# TopLevel.net
KiCad netlist of a schematic drawn in Altium Designer
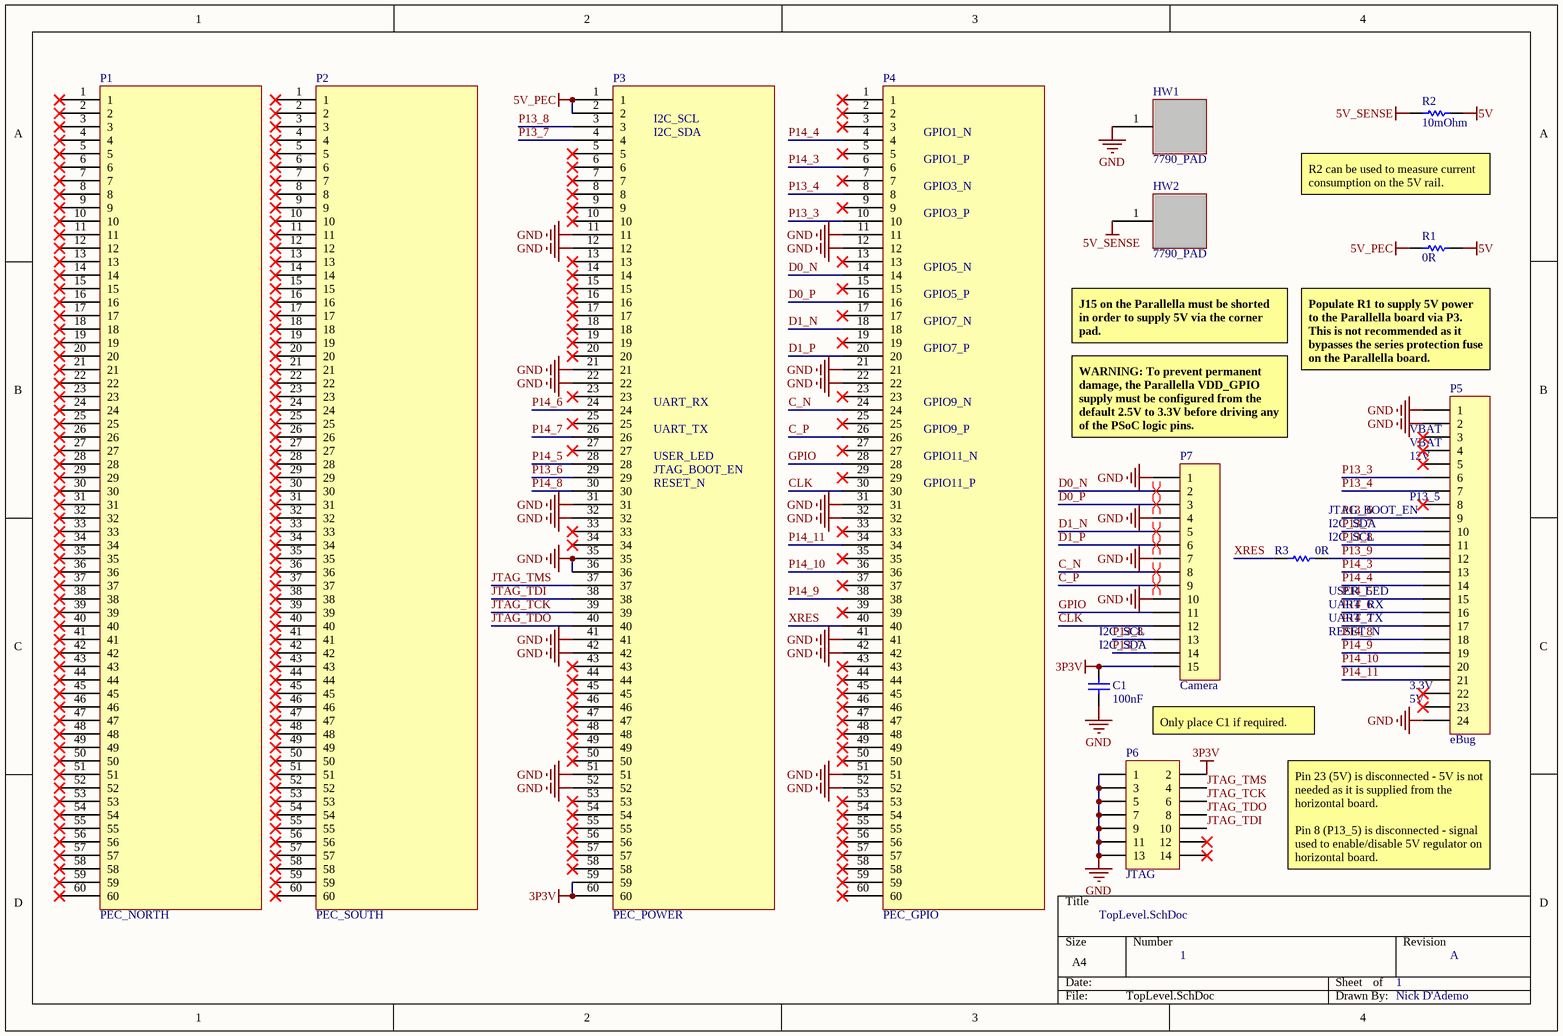
[diagram p0: TopLevel.SchDoc]

(export (version "E")
  (design (tool "Eeschema 10.0.6"))
  (components
    (comp (ref "C1")
      (value "100nF")
      (footprint "CAPC1005N")
      (description "Capacitor, X7R, ±10%, 16V, 0402")
      (fields (field (name "Comment") "Cap") (field (name "PUBLISHER") "Altium Limited"))
      (libsource (lib "Miscellaneous Devices") (part "Cap"))
    )
    (comp (ref "HW1")
      (value "7790_PAD")
      (footprint "7790_PAD")
      (libsource (lib "eBug2014-Parallella-Carrier-V") (part "7790_PAD"))
    )
    (comp (ref "HW2")
      (value "7790_PAD")
      (footprint "7790_PAD")
      (libsource (lib "eBug2014-Parallella-Carrier-V") (part "7790_PAD"))
    )
    (comp (ref "P1")
      (value "PEC_NORTH")
      (footprint "BTH-030-01-F-D-A")
      (description "SAMTEC - BTH-030-01-F-D-A - Conn Micro Terminal HDR 60 POS 0.5mm")
      (libsource (lib "eBug2014-Parallella-Carrier-V") (part "BTH-030-01-F-D-A"))
    )
    (comp (ref "P2")
      (value "PEC_SOUTH")
      (footprint "BTH-030-01-F-D-A")
      (description "SAMTEC - BTH-030-01-F-D-A - Conn Micro Terminal HDR 60 POS 0.5mm")
      (libsource (lib "eBug2014-Parallella-Carrier-V") (part "BTH-030-01-F-D-A"))
    )
    (comp (ref "P3")
      (value "PEC_POWER")
      (footprint "BTH-030-01-F-D-A")
      (description "SAMTEC - BTH-030-01-F-D-A - Conn Micro Terminal HDR 60 POS 0.5mm")
      (libsource (lib "eBug2014-Parallella-Carrier-V") (part "BTH-030-01-F-D-A"))
    )
    (comp (ref "P4")
      (value "PEC_GPIO")
      (footprint "BTH-030-01-F-D-A")
      (description "SAMTEC - BTH-030-01-F-D-A - Conn Micro Terminal HDR 60 POS 0.5mm")
      (libsource (lib "eBug2014-Parallella-Carrier-V") (part "BTH-030-01-F-D-A"))
    )
    (comp (ref "P5")
      (value "eBug")
      (footprint "2-1734592-4_MIRRORED")
      (description "TE CONNECTIVITY - 2-1734592-4 - CONN FPC BOTTOM 24POS 0.50MM R/A")
      (fields (field (name "PUBLISHER") "Altium Limited"))
      (libsource (lib "Miscellaneous Connectors") (part "Header 24"))
    )
    (comp (ref "P6")
      (value "JTAG")
      (footprint "2x7H_2mm")
      (description "Header, 7-Pin, Dual row")
      (fields (field (name "PUBLISHER") "Altium Limited"))
      (libsource (lib "Miscellaneous Connectors") (part "Header 7X2"))
    )
    (comp (ref "P7")
      (value "Camera")
      (footprint "1-1734248-5")
      (fields (field (name "PUBLISHER") "Altium Limited"))
      (libsource (lib "Miscellaneous Connectors") (part "Header 15"))
    )
    (comp (ref "R1")
      (value "0R")
      (footprint "RESC1608M")
      (description "Resistor, ±1%, 0.1W, 0603")
      (fields (field (name "Comment") "Jumper Resistor") (field (name "PUBLISHER") "Altium Limited"))
      (libsource (lib "Miscellaneous Devices") (part "Res1"))
    )
    (comp (ref "R2")
      (value "10mOhm")
      (footprint "RESC6432M")
      (fields (field (name "Comment") "Current Sense Resistor") (field (name "PUBLISHER") "Altium Limited"))
      (libsource (lib "Miscellaneous Devices") (part "Res1"))
    )
    (comp (ref "R3")
      (value "0R")
      (footprint "RESC1608M")
      (description "Resistor, ±1%, 0.1W, 0603")
      (fields (field (name "Comment") "Jumper Resistor") (field (name "PUBLISHER") "Altium Limited"))
      (libsource (lib "Miscellaneous Devices") (part "Res1"))
    )
  )
  (nets
    (net (code "1") (name "/CLK") (class "Default")
      (node (ref "P4") (pin "30") (pinfunction "30_30") (pintype "passive"))
      (node (ref "P7") (pin "12") (pinfunction "12_12") (pintype "passive"))
    )
    (net (code "2") (name "/C_N") (class "Default")
      (node (ref "P4") (pin "24") (pinfunction "24_24") (pintype "passive"))
      (node (ref "P7") (pin "8") (pinfunction "8_8") (pintype "passive"))
    )
    (net (code "3") (name "/C_P") (class "Default")
      (node (ref "P4") (pin "26") (pinfunction "26_26") (pintype "passive"))
      (node (ref "P7") (pin "9") (pinfunction "9_9") (pintype "passive"))
    )
    (net (code "4") (name "/D0_N") (class "Default")
      (node (ref "P4") (pin "14") (pinfunction "14_14") (pintype "passive"))
      (node (ref "P7") (pin "2") (pinfunction "2_2") (pintype "passive"))
    )
    (net (code "5") (name "/D0_P") (class "Default")
      (node (ref "P4") (pin "16") (pinfunction "16_16") (pintype "passive"))
      (node (ref "P7") (pin "3") (pinfunction "3_3") (pintype "passive"))
    )
    (net (code "6") (name "/D1_N") (class "Default")
      (node (ref "P4") (pin "18") (pinfunction "18_18") (pintype "passive"))
      (node (ref "P7") (pin "5") (pinfunction "5_5") (pintype "passive"))
    )
    (net (code "7") (name "/D1_P") (class "Default")
      (node (ref "P4") (pin "20") (pinfunction "20_20") (pintype "passive"))
      (node (ref "P7") (pin "6") (pinfunction "6_6") (pintype "passive"))
    )
    (net (code "8") (name "/GPIO") (class "Default")
      (node (ref "P4") (pin "28") (pinfunction "28_28") (pintype "passive"))
      (node (ref "P7") (pin "11") (pinfunction "11_11") (pintype "passive"))
    )
    (net (code "9") (name "/JTAG_TCK") (class "Default")
      (node (ref "P3") (pin "39") (pinfunction "39_39") (pintype "passive"))
      (node (ref "P6") (pin "6") (pinfunction "6_6") (pintype "passive"))
    )
    (net (code "10") (name "/JTAG_TDI") (class "Default")
      (node (ref "P3") (pin "38") (pinfunction "38_38") (pintype "passive"))
      (node (ref "P6") (pin "10") (pinfunction "10_10") (pintype "passive"))
    )
    (net (code "11") (name "/JTAG_TDO") (class "Default")
      (node (ref "P3") (pin "40") (pinfunction "40_40") (pintype "passive"))
      (node (ref "P6") (pin "8") (pinfunction "8_8") (pintype "passive"))
    )
    (net (code "12") (name "/JTAG_TMS") (class "Default")
      (node (ref "P3") (pin "37") (pinfunction "37_37") (pintype "passive"))
      (node (ref "P6") (pin "4") (pinfunction "4_4") (pintype "passive"))
    )
    (net (code "13") (name "/P13_3") (class "Default")
      (node (ref "P4") (pin "10") (pinfunction "10_10") (pintype "passive"))
      (node (ref "P5") (pin "6") (pinfunction "6_6") (pintype "passive"))
    )
    (net (code "14") (name "/P13_4") (class "Default")
      (node (ref "P4") (pin "8") (pinfunction "8_8") (pintype "passive"))
      (node (ref "P5") (pin "7") (pinfunction "7_7") (pintype "passive"))
    )
    (net (code "15") (name "/P13_6") (class "Default")
      (node (ref "P3") (pin "29") (pinfunction "29_29") (pintype "passive"))
      (node (ref "P5") (pin "9") (pinfunction "9_9") (pintype "passive"))
    )
    (net (code "16") (name "/P13_7") (class "Default")
      (node (ref "P3") (pin "4") (pinfunction "4_4") (pintype "passive"))
      (node (ref "P5") (pin "10") (pinfunction "10_10") (pintype "passive"))
      (node (ref "P7") (pin "14") (pinfunction "14_14") (pintype "passive"))
    )
    (net (code "17") (name "/P13_8") (class "Default")
      (node (ref "P3") (pin "3") (pinfunction "3_3") (pintype "passive"))
      (node (ref "P5") (pin "11") (pinfunction "11_11") (pintype "passive"))
      (node (ref "P7") (pin "13") (pinfunction "13_13") (pintype "passive"))
    )
    (net (code "18") (name "/P13_9") (class "Default")
      (node (ref "P5") (pin "12") (pinfunction "12_12") (pintype "passive"))
      (node (ref "R3") (pin "1") (pinfunction "1_1") (pintype "passive"))
    )
    (net (code "19") (name "/P14_3") (class "Default")
      (node (ref "P4") (pin "6") (pinfunction "6_6") (pintype "passive"))
      (node (ref "P5") (pin "13") (pinfunction "13_13") (pintype "passive"))
    )
    (net (code "20") (name "/P14_4") (class "Default")
      (node (ref "P4") (pin "4") (pinfunction "4_4") (pintype "passive"))
      (node (ref "P5") (pin "14") (pinfunction "14_14") (pintype "passive"))
    )
    (net (code "21") (name "/P14_5") (class "Default")
      (node (ref "P3") (pin "28") (pinfunction "28_28") (pintype "passive"))
      (node (ref "P5") (pin "15") (pinfunction "15_15") (pintype "passive"))
    )
    (net (code "22") (name "/P14_6") (class "Default")
      (node (ref "P3") (pin "24") (pinfunction "24_24") (pintype "passive"))
      (node (ref "P5") (pin "16") (pinfunction "16_16") (pintype "passive"))
    )
    (net (code "23") (name "/P14_7") (class "Default")
      (node (ref "P3") (pin "26") (pinfunction "26_26") (pintype "passive"))
      (node (ref "P5") (pin "17") (pinfunction "17_17") (pintype "passive"))
    )
    (net (code "24") (name "/P14_8") (class "Default")
      (node (ref "P3") (pin "30") (pinfunction "30_30") (pintype "passive"))
      (node (ref "P5") (pin "18") (pinfunction "18_18") (pintype "passive"))
    )
    (net (code "25") (name "/P14_9") (class "Default")
      (node (ref "P4") (pin "38") (pinfunction "38_38") (pintype "passive"))
      (node (ref "P5") (pin "19") (pinfunction "19_19") (pintype "passive"))
    )
    (net (code "26") (name "/P14_10") (class "Default")
      (node (ref "P4") (pin "36") (pinfunction "36_36") (pintype "passive"))
      (node (ref "P5") (pin "20") (pinfunction "20_20") (pintype "passive"))
    )
    (net (code "27") (name "/P14_11") (class "Default")
      (node (ref "P4") (pin "34") (pinfunction "34_34") (pintype "passive"))
      (node (ref "P5") (pin "21") (pinfunction "21_21") (pintype "passive"))
    )
    (net (code "28") (name "/XRES") (class "Default")
      (node (ref "P4") (pin "40") (pinfunction "40_40") (pintype "passive"))
      (node (ref "R3") (pin "2") (pinfunction "2_2") (pintype "passive"))
    )
    (net (code "29") (name "3P3V") (class "Default")
      (node (ref "C1") (pin "2") (pinfunction "2_2") (pintype "passive"))
      (node (ref "P3") (pin "59") (pinfunction "59_59") (pintype "passive"))
      (node (ref "P3") (pin "60") (pinfunction "60_60") (pintype "passive"))
      (node (ref "P6") (pin "2") (pinfunction "2_2") (pintype "passive"))
      (node (ref "P7") (pin "15") (pinfunction "15_15") (pintype "passive"))
    )
    (net (code "30") (name "5V") (class "Default")
      (node (ref "R1") (pin "1") (pinfunction "1_1") (pintype "passive"))
      (node (ref "R2") (pin "1") (pinfunction "1_1") (pintype "passive"))
    )
    (net (code "31") (name "5V_PEC") (class "Default")
      (node (ref "P3") (pin "1") (pinfunction "1_1") (pintype "passive"))
      (node (ref "P3") (pin "2") (pinfunction "2_2") (pintype "passive"))
      (node (ref "R1") (pin "2") (pinfunction "2_2") (pintype "passive"))
    )
    (net (code "32") (name "5V_SENSE") (class "Default")
      (node (ref "HW2") (pin "1") (pintype "passive"))
      (node (ref "R2") (pin "2") (pinfunction "2_2") (pintype "passive"))
    )
    (net (code "33") (name "GND") (class "Default")
      (node (ref "C1") (pin "1") (pinfunction "1_1") (pintype "passive"))
      (node (ref "HW1") (pin "1") (pintype "passive"))
      (node (ref "P3") (pin "11") (pinfunction "11_11") (pintype "passive"))
      (node (ref "P3") (pin "12") (pinfunction "12_12") (pintype "passive"))
      (node (ref "P3") (pin "21") (pinfunction "21_21") (pintype "passive"))
      (node (ref "P3") (pin "22") (pinfunction "22_22") (pintype "passive"))
      (node (ref "P3") (pin "31") (pinfunction "31_31") (pintype "passive"))
      (node (ref "P3") (pin "32") (pinfunction "32_32") (pintype "passive"))
      (node (ref "P3") (pin "35") (pinfunction "35_35") (pintype "passive"))
      (node (ref "P3") (pin "36") (pinfunction "36_36") (pintype "passive"))
      (node (ref "P3") (pin "41") (pinfunction "41_41") (pintype "passive"))
      (node (ref "P3") (pin "42") (pinfunction "42_42") (pintype "passive"))
      (node (ref "P3") (pin "51") (pinfunction "51_51") (pintype "passive"))
      (node (ref "P3") (pin "52") (pinfunction "52_52") (pintype "passive"))
      (node (ref "P4") (pin "11") (pinfunction "11_11") (pintype "passive"))
      (node (ref "P4") (pin "12") (pinfunction "12_12") (pintype "passive"))
      (node (ref "P4") (pin "21") (pinfunction "21_21") (pintype "passive"))
      (node (ref "P4") (pin "22") (pinfunction "22_22") (pintype "passive"))
      (node (ref "P4") (pin "31") (pinfunction "31_31") (pintype "passive"))
      (node (ref "P4") (pin "32") (pinfunction "32_32") (pintype "passive"))
      (node (ref "P4") (pin "41") (pinfunction "41_41") (pintype "passive"))
      (node (ref "P4") (pin "42") (pinfunction "42_42") (pintype "passive"))
      (node (ref "P4") (pin "51") (pinfunction "51_51") (pintype "passive"))
      (node (ref "P4") (pin "52") (pinfunction "52_52") (pintype "passive"))
      (node (ref "P5") (pin "1") (pinfunction "1_1") (pintype "passive"))
      (node (ref "P5") (pin "2") (pinfunction "2_2") (pintype "passive"))
      (node (ref "P5") (pin "24") (pinfunction "24_24") (pintype "passive"))
      (node (ref "P6") (pin "1") (pinfunction "1_1") (pintype "passive"))
      (node (ref "P6") (pin "11") (pinfunction "11_11") (pintype "passive"))
      (node (ref "P6") (pin "13") (pinfunction "13_13") (pintype "passive"))
      (node (ref "P6") (pin "3") (pinfunction "3_3") (pintype "passive"))
      (node (ref "P6") (pin "5") (pinfunction "5_5") (pintype "passive"))
      (node (ref "P6") (pin "7") (pinfunction "7_7") (pintype "passive"))
      (node (ref "P6") (pin "9") (pinfunction "9_9") (pintype "passive"))
      (node (ref "P7") (pin "1") (pinfunction "1_1") (pintype "passive"))
      (node (ref "P7") (pin "10") (pinfunction "10_10") (pintype "passive"))
      (node (ref "P7") (pin "4") (pinfunction "4_4") (pintype "passive"))
      (node (ref "P7") (pin "7") (pinfunction "7_7") (pintype "passive"))
    )
    (net (code "34") (name "unconnected-(P1-Pad1)") (class "Default")
      (node (ref "P1") (pin "1") (pinfunction "1_1") (pintype "passive+no_connect"))
    )
    (net (code "35") (name "unconnected-(P1-Pad2)") (class "Default")
      (node (ref "P1") (pin "2") (pinfunction "2_2") (pintype "passive+no_connect"))
    )
    (net (code "36") (name "unconnected-(P1-Pad3)") (class "Default")
      (node (ref "P1") (pin "3") (pinfunction "3_3") (pintype "passive+no_connect"))
    )
    (net (code "37") (name "unconnected-(P1-Pad4)") (class "Default")
      (node (ref "P1") (pin "4") (pinfunction "4_4") (pintype "passive+no_connect"))
    )
    (net (code "38") (name "unconnected-(P1-Pad5)") (class "Default")
      (node (ref "P1") (pin "5") (pinfunction "5_5") (pintype "passive+no_connect"))
    )
    (net (code "39") (name "unconnected-(P1-Pad6)") (class "Default")
      (node (ref "P1") (pin "6") (pinfunction "6_6") (pintype "passive+no_connect"))
    )
    (net (code "40") (name "unconnected-(P1-Pad7)") (class "Default")
      (node (ref "P1") (pin "7") (pinfunction "7_7") (pintype "passive+no_connect"))
    )
    (net (code "41") (name "unconnected-(P1-Pad8)") (class "Default")
      (node (ref "P1") (pin "8") (pinfunction "8_8") (pintype "passive+no_connect"))
    )
    (net (code "42") (name "unconnected-(P1-Pad9)") (class "Default")
      (node (ref "P1") (pin "9") (pinfunction "9_9") (pintype "passive+no_connect"))
    )
    (net (code "43") (name "unconnected-(P1-Pad10)") (class "Default")
      (node (ref "P1") (pin "10") (pinfunction "10_10") (pintype "passive+no_connect"))
    )
    (net (code "44") (name "unconnected-(P1-Pad11)") (class "Default")
      (node (ref "P1") (pin "11") (pinfunction "11_11") (pintype "passive+no_connect"))
    )
    (net (code "45") (name "unconnected-(P1-Pad12)") (class "Default")
      (node (ref "P1") (pin "12") (pinfunction "12_12") (pintype "passive+no_connect"))
    )
    (net (code "46") (name "unconnected-(P1-Pad13)") (class "Default")
      (node (ref "P1") (pin "13") (pinfunction "13_13") (pintype "passive+no_connect"))
    )
    (net (code "47") (name "unconnected-(P1-Pad14)") (class "Default")
      (node (ref "P1") (pin "14") (pinfunction "14_14") (pintype "passive+no_connect"))
    )
    (net (code "48") (name "unconnected-(P1-Pad15)") (class "Default")
      (node (ref "P1") (pin "15") (pinfunction "15_15") (pintype "passive+no_connect"))
    )
    (net (code "49") (name "unconnected-(P1-Pad16)") (class "Default")
      (node (ref "P1") (pin "16") (pinfunction "16_16") (pintype "passive+no_connect"))
    )
    (net (code "50") (name "unconnected-(P1-Pad17)") (class "Default")
      (node (ref "P1") (pin "17") (pinfunction "17_17") (pintype "passive+no_connect"))
    )
    (net (code "51") (name "unconnected-(P1-Pad18)") (class "Default")
      (node (ref "P1") (pin "18") (pinfunction "18_18") (pintype "passive+no_connect"))
    )
    (net (code "52") (name "unconnected-(P1-Pad19)") (class "Default")
      (node (ref "P1") (pin "19") (pinfunction "19_19") (pintype "passive+no_connect"))
    )
    (net (code "53") (name "unconnected-(P1-Pad20)") (class "Default")
      (node (ref "P1") (pin "20") (pinfunction "20_20") (pintype "passive+no_connect"))
    )
    (net (code "54") (name "unconnected-(P1-Pad21)") (class "Default")
      (node (ref "P1") (pin "21") (pinfunction "21_21") (pintype "passive+no_connect"))
    )
    (net (code "55") (name "unconnected-(P1-Pad22)") (class "Default")
      (node (ref "P1") (pin "22") (pinfunction "22_22") (pintype "passive+no_connect"))
    )
    (net (code "56") (name "unconnected-(P1-Pad23)") (class "Default")
      (node (ref "P1") (pin "23") (pinfunction "23_23") (pintype "passive+no_connect"))
    )
    (net (code "57") (name "unconnected-(P1-Pad24)") (class "Default")
      (node (ref "P1") (pin "24") (pinfunction "24_24") (pintype "passive+no_connect"))
    )
    (net (code "58") (name "unconnected-(P1-Pad25)") (class "Default")
      (node (ref "P1") (pin "25") (pinfunction "25_25") (pintype "passive+no_connect"))
    )
    (net (code "59") (name "unconnected-(P1-Pad26)") (class "Default")
      (node (ref "P1") (pin "26") (pinfunction "26_26") (pintype "passive+no_connect"))
    )
    (net (code "60") (name "unconnected-(P1-Pad27)") (class "Default")
      (node (ref "P1") (pin "27") (pinfunction "27_27") (pintype "passive+no_connect"))
    )
    (net (code "61") (name "unconnected-(P1-Pad28)") (class "Default")
      (node (ref "P1") (pin "28") (pinfunction "28_28") (pintype "passive+no_connect"))
    )
    (net (code "62") (name "unconnected-(P1-Pad29)") (class "Default")
      (node (ref "P1") (pin "29") (pinfunction "29_29") (pintype "passive+no_connect"))
    )
    (net (code "63") (name "unconnected-(P1-Pad30)") (class "Default")
      (node (ref "P1") (pin "30") (pinfunction "30_30") (pintype "passive+no_connect"))
    )
    (net (code "64") (name "unconnected-(P1-Pad31)") (class "Default")
      (node (ref "P1") (pin "31") (pinfunction "31_31") (pintype "passive+no_connect"))
    )
    (net (code "65") (name "unconnected-(P1-Pad32)") (class "Default")
      (node (ref "P1") (pin "32") (pinfunction "32_32") (pintype "passive+no_connect"))
    )
    (net (code "66") (name "unconnected-(P1-Pad33)") (class "Default")
      (node (ref "P1") (pin "33") (pinfunction "33_33") (pintype "passive+no_connect"))
    )
    (net (code "67") (name "unconnected-(P1-Pad34)") (class "Default")
      (node (ref "P1") (pin "34") (pinfunction "34_34") (pintype "passive+no_connect"))
    )
    (net (code "68") (name "unconnected-(P1-Pad35)") (class "Default")
      (node (ref "P1") (pin "35") (pinfunction "35_35") (pintype "passive+no_connect"))
    )
    (net (code "69") (name "unconnected-(P1-Pad36)") (class "Default")
      (node (ref "P1") (pin "36") (pinfunction "36_36") (pintype "passive+no_connect"))
    )
    (net (code "70") (name "unconnected-(P1-Pad37)") (class "Default")
      (node (ref "P1") (pin "37") (pinfunction "37_37") (pintype "passive+no_connect"))
    )
    (net (code "71") (name "unconnected-(P1-Pad38)") (class "Default")
      (node (ref "P1") (pin "38") (pinfunction "38_38") (pintype "passive+no_connect"))
    )
    (net (code "72") (name "unconnected-(P1-Pad39)") (class "Default")
      (node (ref "P1") (pin "39") (pinfunction "39_39") (pintype "passive+no_connect"))
    )
    (net (code "73") (name "unconnected-(P1-Pad40)") (class "Default")
      (node (ref "P1") (pin "40") (pinfunction "40_40") (pintype "passive+no_connect"))
    )
    (net (code "74") (name "unconnected-(P1-Pad41)") (class "Default")
      (node (ref "P1") (pin "41") (pinfunction "41_41") (pintype "passive+no_connect"))
    )
    (net (code "75") (name "unconnected-(P1-Pad42)") (class "Default")
      (node (ref "P1") (pin "42") (pinfunction "42_42") (pintype "passive+no_connect"))
    )
    (net (code "76") (name "unconnected-(P1-Pad43)") (class "Default")
      (node (ref "P1") (pin "43") (pinfunction "43_43") (pintype "passive+no_connect"))
    )
    (net (code "77") (name "unconnected-(P1-Pad44)") (class "Default")
      (node (ref "P1") (pin "44") (pinfunction "44_44") (pintype "passive+no_connect"))
    )
    (net (code "78") (name "unconnected-(P1-Pad45)") (class "Default")
      (node (ref "P1") (pin "45") (pinfunction "45_45") (pintype "passive+no_connect"))
    )
    (net (code "79") (name "unconnected-(P1-Pad46)") (class "Default")
      (node (ref "P1") (pin "46") (pinfunction "46_46") (pintype "passive+no_connect"))
    )
    (net (code "80") (name "unconnected-(P1-Pad47)") (class "Default")
      (node (ref "P1") (pin "47") (pinfunction "47_47") (pintype "passive+no_connect"))
    )
    (net (code "81") (name "unconnected-(P1-Pad48)") (class "Default")
      (node (ref "P1") (pin "48") (pinfunction "48_48") (pintype "passive+no_connect"))
    )
    (net (code "82") (name "unconnected-(P1-Pad49)") (class "Default")
      (node (ref "P1") (pin "49") (pinfunction "49_49") (pintype "passive+no_connect"))
    )
    (net (code "83") (name "unconnected-(P1-Pad50)") (class "Default")
      (node (ref "P1") (pin "50") (pinfunction "50_50") (pintype "passive+no_connect"))
    )
    (net (code "84") (name "unconnected-(P1-Pad51)") (class "Default")
      (node (ref "P1") (pin "51") (pinfunction "51_51") (pintype "passive+no_connect"))
    )
    (net (code "85") (name "unconnected-(P1-Pad52)") (class "Default")
      (node (ref "P1") (pin "52") (pinfunction "52_52") (pintype "passive+no_connect"))
    )
    (net (code "86") (name "unconnected-(P1-Pad53)") (class "Default")
      (node (ref "P1") (pin "53") (pinfunction "53_53") (pintype "passive+no_connect"))
    )
    (net (code "87") (name "unconnected-(P1-Pad54)") (class "Default")
      (node (ref "P1") (pin "54") (pinfunction "54_54") (pintype "passive+no_connect"))
    )
    (net (code "88") (name "unconnected-(P1-Pad55)") (class "Default")
      (node (ref "P1") (pin "55") (pinfunction "55_55") (pintype "passive+no_connect"))
    )
    (net (code "89") (name "unconnected-(P1-Pad56)") (class "Default")
      (node (ref "P1") (pin "56") (pinfunction "56_56") (pintype "passive+no_connect"))
    )
    (net (code "90") (name "unconnected-(P1-Pad57)") (class "Default")
      (node (ref "P1") (pin "57") (pinfunction "57_57") (pintype "passive+no_connect"))
    )
    (net (code "91") (name "unconnected-(P1-Pad58)") (class "Default")
      (node (ref "P1") (pin "58") (pinfunction "58_58") (pintype "passive+no_connect"))
    )
    (net (code "92") (name "unconnected-(P1-Pad59)") (class "Default")
      (node (ref "P1") (pin "59") (pinfunction "59_59") (pintype "passive+no_connect"))
    )
    (net (code "93") (name "unconnected-(P1-Pad60)") (class "Default")
      (node (ref "P1") (pin "60") (pinfunction "60_60") (pintype "passive+no_connect"))
    )
    (net (code "94") (name "unconnected-(P2-Pad1)") (class "Default")
      (node (ref "P2") (pin "1") (pinfunction "1_1") (pintype "passive+no_connect"))
    )
    (net (code "95") (name "unconnected-(P2-Pad2)") (class "Default")
      (node (ref "P2") (pin "2") (pinfunction "2_2") (pintype "passive+no_connect"))
    )
    (net (code "96") (name "unconnected-(P2-Pad3)") (class "Default")
      (node (ref "P2") (pin "3") (pinfunction "3_3") (pintype "passive+no_connect"))
    )
    (net (code "97") (name "unconnected-(P2-Pad4)") (class "Default")
      (node (ref "P2") (pin "4") (pinfunction "4_4") (pintype "passive+no_connect"))
    )
    (net (code "98") (name "unconnected-(P2-Pad5)") (class "Default")
      (node (ref "P2") (pin "5") (pinfunction "5_5") (pintype "passive+no_connect"))
    )
    (net (code "99") (name "unconnected-(P2-Pad6)") (class "Default")
      (node (ref "P2") (pin "6") (pinfunction "6_6") (pintype "passive+no_connect"))
    )
    (net (code "100") (name "unconnected-(P2-Pad7)") (class "Default")
      (node (ref "P2") (pin "7") (pinfunction "7_7") (pintype "passive+no_connect"))
    )
    (net (code "101") (name "unconnected-(P2-Pad8)") (class "Default")
      (node (ref "P2") (pin "8") (pinfunction "8_8") (pintype "passive+no_connect"))
    )
    (net (code "102") (name "unconnected-(P2-Pad9)") (class "Default")
      (node (ref "P2") (pin "9") (pinfunction "9_9") (pintype "passive+no_connect"))
    )
    (net (code "103") (name "unconnected-(P2-Pad10)") (class "Default")
      (node (ref "P2") (pin "10") (pinfunction "10_10") (pintype "passive+no_connect"))
    )
    (net (code "104") (name "unconnected-(P2-Pad11)") (class "Default")
      (node (ref "P2") (pin "11") (pinfunction "11_11") (pintype "passive+no_connect"))
    )
    (net (code "105") (name "unconnected-(P2-Pad12)") (class "Default")
      (node (ref "P2") (pin "12") (pinfunction "12_12") (pintype "passive+no_connect"))
    )
    (net (code "106") (name "unconnected-(P2-Pad13)") (class "Default")
      (node (ref "P2") (pin "13") (pinfunction "13_13") (pintype "passive+no_connect"))
    )
    (net (code "107") (name "unconnected-(P2-Pad14)") (class "Default")
      (node (ref "P2") (pin "14") (pinfunction "14_14") (pintype "passive+no_connect"))
    )
    (net (code "108") (name "unconnected-(P2-Pad15)") (class "Default")
      (node (ref "P2") (pin "15") (pinfunction "15_15") (pintype "passive+no_connect"))
    )
    (net (code "109") (name "unconnected-(P2-Pad16)") (class "Default")
      (node (ref "P2") (pin "16") (pinfunction "16_16") (pintype "passive+no_connect"))
    )
    (net (code "110") (name "unconnected-(P2-Pad17)") (class "Default")
      (node (ref "P2") (pin "17") (pinfunction "17_17") (pintype "passive+no_connect"))
    )
    (net (code "111") (name "unconnected-(P2-Pad18)") (class "Default")
      (node (ref "P2") (pin "18") (pinfunction "18_18") (pintype "passive+no_connect"))
    )
    (net (code "112") (name "unconnected-(P2-Pad19)") (class "Default")
      (node (ref "P2") (pin "19") (pinfunction "19_19") (pintype "passive+no_connect"))
    )
    (net (code "113") (name "unconnected-(P2-Pad20)") (class "Default")
      (node (ref "P2") (pin "20") (pinfunction "20_20") (pintype "passive+no_connect"))
    )
    (net (code "114") (name "unconnected-(P2-Pad21)") (class "Default")
      (node (ref "P2") (pin "21") (pinfunction "21_21") (pintype "passive+no_connect"))
    )
    (net (code "115") (name "unconnected-(P2-Pad22)") (class "Default")
      (node (ref "P2") (pin "22") (pinfunction "22_22") (pintype "passive+no_connect"))
    )
    (net (code "116") (name "unconnected-(P2-Pad23)") (class "Default")
      (node (ref "P2") (pin "23") (pinfunction "23_23") (pintype "passive+no_connect"))
    )
    (net (code "117") (name "unconnected-(P2-Pad24)") (class "Default")
      (node (ref "P2") (pin "24") (pinfunction "24_24") (pintype "passive+no_connect"))
    )
    (net (code "118") (name "unconnected-(P2-Pad25)") (class "Default")
      (node (ref "P2") (pin "25") (pinfunction "25_25") (pintype "passive+no_connect"))
    )
    (net (code "119") (name "unconnected-(P2-Pad26)") (class "Default")
      (node (ref "P2") (pin "26") (pinfunction "26_26") (pintype "passive+no_connect"))
    )
    (net (code "120") (name "unconnected-(P2-Pad27)") (class "Default")
      (node (ref "P2") (pin "27") (pinfunction "27_27") (pintype "passive+no_connect"))
    )
    (net (code "121") (name "unconnected-(P2-Pad28)") (class "Default")
      (node (ref "P2") (pin "28") (pinfunction "28_28") (pintype "passive+no_connect"))
    )
    (net (code "122") (name "unconnected-(P2-Pad29)") (class "Default")
      (node (ref "P2") (pin "29") (pinfunction "29_29") (pintype "passive+no_connect"))
    )
    (net (code "123") (name "unconnected-(P2-Pad30)") (class "Default")
      (node (ref "P2") (pin "30") (pinfunction "30_30") (pintype "passive+no_connect"))
    )
    (net (code "124") (name "unconnected-(P2-Pad31)") (class "Default")
      (node (ref "P2") (pin "31") (pinfunction "31_31") (pintype "passive+no_connect"))
    )
    (net (code "125") (name "unconnected-(P2-Pad32)") (class "Default")
      (node (ref "P2") (pin "32") (pinfunction "32_32") (pintype "passive+no_connect"))
    )
    (net (code "126") (name "unconnected-(P2-Pad33)") (class "Default")
      (node (ref "P2") (pin "33") (pinfunction "33_33") (pintype "passive+no_connect"))
    )
    (net (code "127") (name "unconnected-(P2-Pad34)") (class "Default")
      (node (ref "P2") (pin "34") (pinfunction "34_34") (pintype "passive+no_connect"))
    )
    (net (code "128") (name "unconnected-(P2-Pad35)") (class "Default")
      (node (ref "P2") (pin "35") (pinfunction "35_35") (pintype "passive+no_connect"))
    )
    (net (code "129") (name "unconnected-(P2-Pad36)") (class "Default")
      (node (ref "P2") (pin "36") (pinfunction "36_36") (pintype "passive+no_connect"))
    )
    (net (code "130") (name "unconnected-(P2-Pad37)") (class "Default")
      (node (ref "P2") (pin "37") (pinfunction "37_37") (pintype "passive+no_connect"))
    )
    (net (code "131") (name "unconnected-(P2-Pad38)") (class "Default")
      (node (ref "P2") (pin "38") (pinfunction "38_38") (pintype "passive+no_connect"))
    )
    (net (code "132") (name "unconnected-(P2-Pad39)") (class "Default")
      (node (ref "P2") (pin "39") (pinfunction "39_39") (pintype "passive+no_connect"))
    )
    (net (code "133") (name "unconnected-(P2-Pad40)") (class "Default")
      (node (ref "P2") (pin "40") (pinfunction "40_40") (pintype "passive+no_connect"))
    )
    (net (code "134") (name "unconnected-(P2-Pad41)") (class "Default")
      (node (ref "P2") (pin "41") (pinfunction "41_41") (pintype "passive+no_connect"))
    )
    (net (code "135") (name "unconnected-(P2-Pad42)") (class "Default")
      (node (ref "P2") (pin "42") (pinfunction "42_42") (pintype "passive+no_connect"))
    )
    (net (code "136") (name "unconnected-(P2-Pad43)") (class "Default")
      (node (ref "P2") (pin "43") (pinfunction "43_43") (pintype "passive+no_connect"))
    )
    (net (code "137") (name "unconnected-(P2-Pad44)") (class "Default")
      (node (ref "P2") (pin "44") (pinfunction "44_44") (pintype "passive+no_connect"))
    )
    (net (code "138") (name "unconnected-(P2-Pad45)") (class "Default")
      (node (ref "P2") (pin "45") (pinfunction "45_45") (pintype "passive+no_connect"))
    )
    (net (code "139") (name "unconnected-(P2-Pad46)") (class "Default")
      (node (ref "P2") (pin "46") (pinfunction "46_46") (pintype "passive+no_connect"))
    )
    (net (code "140") (name "unconnected-(P2-Pad47)") (class "Default")
      (node (ref "P2") (pin "47") (pinfunction "47_47") (pintype "passive+no_connect"))
    )
    (net (code "141") (name "unconnected-(P2-Pad48)") (class "Default")
      (node (ref "P2") (pin "48") (pinfunction "48_48") (pintype "passive+no_connect"))
    )
    (net (code "142") (name "unconnected-(P2-Pad49)") (class "Default")
      (node (ref "P2") (pin "49") (pinfunction "49_49") (pintype "passive+no_connect"))
    )
    (net (code "143") (name "unconnected-(P2-Pad50)") (class "Default")
      (node (ref "P2") (pin "50") (pinfunction "50_50") (pintype "passive+no_connect"))
    )
    (net (code "144") (name "unconnected-(P2-Pad51)") (class "Default")
      (node (ref "P2") (pin "51") (pinfunction "51_51") (pintype "passive+no_connect"))
    )
    (net (code "145") (name "unconnected-(P2-Pad52)") (class "Default")
      (node (ref "P2") (pin "52") (pinfunction "52_52") (pintype "passive+no_connect"))
    )
    (net (code "146") (name "unconnected-(P2-Pad53)") (class "Default")
      (node (ref "P2") (pin "53") (pinfunction "53_53") (pintype "passive+no_connect"))
    )
    (net (code "147") (name "unconnected-(P2-Pad54)") (class "Default")
      (node (ref "P2") (pin "54") (pinfunction "54_54") (pintype "passive+no_connect"))
    )
    (net (code "148") (name "unconnected-(P2-Pad55)") (class "Default")
      (node (ref "P2") (pin "55") (pinfunction "55_55") (pintype "passive+no_connect"))
    )
    (net (code "149") (name "unconnected-(P2-Pad56)") (class "Default")
      (node (ref "P2") (pin "56") (pinfunction "56_56") (pintype "passive+no_connect"))
    )
    (net (code "150") (name "unconnected-(P2-Pad57)") (class "Default")
      (node (ref "P2") (pin "57") (pinfunction "57_57") (pintype "passive+no_connect"))
    )
    (net (code "151") (name "unconnected-(P2-Pad58)") (class "Default")
      (node (ref "P2") (pin "58") (pinfunction "58_58") (pintype "passive+no_connect"))
    )
    (net (code "152") (name "unconnected-(P2-Pad59)") (class "Default")
      (node (ref "P2") (pin "59") (pinfunction "59_59") (pintype "passive+no_connect"))
    )
    (net (code "153") (name "unconnected-(P2-Pad60)") (class "Default")
      (node (ref "P2") (pin "60") (pinfunction "60_60") (pintype "passive+no_connect"))
    )
    (net (code "154") (name "unconnected-(P3-Pad5)") (class "Default")
      (node (ref "P3") (pin "5") (pinfunction "5_5") (pintype "passive+no_connect"))
    )
    (net (code "155") (name "unconnected-(P3-Pad6)") (class "Default")
      (node (ref "P3") (pin "6") (pinfunction "6_6") (pintype "passive+no_connect"))
    )
    (net (code "156") (name "unconnected-(P3-Pad7)") (class "Default")
      (node (ref "P3") (pin "7") (pinfunction "7_7") (pintype "passive+no_connect"))
    )
    (net (code "157") (name "unconnected-(P3-Pad8)") (class "Default")
      (node (ref "P3") (pin "8") (pinfunction "8_8") (pintype "passive+no_connect"))
    )
    (net (code "158") (name "unconnected-(P3-Pad9)") (class "Default")
      (node (ref "P3") (pin "9") (pinfunction "9_9") (pintype "passive+no_connect"))
    )
    (net (code "159") (name "unconnected-(P3-Pad10)") (class "Default")
      (node (ref "P3") (pin "10") (pinfunction "10_10") (pintype "passive+no_connect"))
    )
    (net (code "160") (name "unconnected-(P3-Pad13)") (class "Default")
      (node (ref "P3") (pin "13") (pinfunction "13_13") (pintype "passive+no_connect"))
    )
    (net (code "161") (name "unconnected-(P3-Pad14)") (class "Default")
      (node (ref "P3") (pin "14") (pinfunction "14_14") (pintype "passive+no_connect"))
    )
    (net (code "162") (name "unconnected-(P3-Pad15)") (class "Default")
      (node (ref "P3") (pin "15") (pinfunction "15_15") (pintype "passive+no_connect"))
    )
    (net (code "163") (name "unconnected-(P3-Pad16)") (class "Default")
      (node (ref "P3") (pin "16") (pinfunction "16_16") (pintype "passive+no_connect"))
    )
    (net (code "164") (name "unconnected-(P3-Pad17)") (class "Default")
      (node (ref "P3") (pin "17") (pinfunction "17_17") (pintype "passive+no_connect"))
    )
    (net (code "165") (name "unconnected-(P3-Pad18)") (class "Default")
      (node (ref "P3") (pin "18") (pinfunction "18_18") (pintype "passive+no_connect"))
    )
    (net (code "166") (name "unconnected-(P3-Pad19)") (class "Default")
      (node (ref "P3") (pin "19") (pinfunction "19_19") (pintype "passive+no_connect"))
    )
    (net (code "167") (name "unconnected-(P3-Pad20)") (class "Default")
      (node (ref "P3") (pin "20") (pinfunction "20_20") (pintype "passive+no_connect"))
    )
    (net (code "168") (name "unconnected-(P3-Pad23)") (class "Default")
      (node (ref "P3") (pin "23") (pinfunction "23_23") (pintype "passive+no_connect"))
    )
    (net (code "169") (name "unconnected-(P3-Pad25)") (class "Default")
      (node (ref "P3") (pin "25") (pinfunction "25_25") (pintype "passive+no_connect"))
    )
    (net (code "170") (name "unconnected-(P3-Pad27)") (class "Default")
      (node (ref "P3") (pin "27") (pinfunction "27_27") (pintype "passive+no_connect"))
    )
    (net (code "171") (name "unconnected-(P3-Pad33)") (class "Default")
      (node (ref "P3") (pin "33") (pinfunction "33_33") (pintype "passive+no_connect"))
    )
    (net (code "172") (name "unconnected-(P3-Pad34)") (class "Default")
      (node (ref "P3") (pin "34") (pinfunction "34_34") (pintype "passive+no_connect"))
    )
    (net (code "173") (name "unconnected-(P3-Pad43)") (class "Default")
      (node (ref "P3") (pin "43") (pinfunction "43_43") (pintype "passive+no_connect"))
    )
    (net (code "174") (name "unconnected-(P3-Pad44)") (class "Default")
      (node (ref "P3") (pin "44") (pinfunction "44_44") (pintype "passive+no_connect"))
    )
    (net (code "175") (name "unconnected-(P3-Pad45)") (class "Default")
      (node (ref "P3") (pin "45") (pinfunction "45_45") (pintype "passive+no_connect"))
    )
    (net (code "176") (name "unconnected-(P3-Pad46)") (class "Default")
      (node (ref "P3") (pin "46") (pinfunction "46_46") (pintype "passive+no_connect"))
    )
    (net (code "177") (name "unconnected-(P3-Pad47)") (class "Default")
      (node (ref "P3") (pin "47") (pinfunction "47_47") (pintype "passive+no_connect"))
    )
    (net (code "178") (name "unconnected-(P3-Pad48)") (class "Default")
      (node (ref "P3") (pin "48") (pinfunction "48_48") (pintype "passive+no_connect"))
    )
    (net (code "179") (name "unconnected-(P3-Pad49)") (class "Default")
      (node (ref "P3") (pin "49") (pinfunction "49_49") (pintype "passive+no_connect"))
    )
    (net (code "180") (name "unconnected-(P3-Pad50)") (class "Default")
      (node (ref "P3") (pin "50") (pinfunction "50_50") (pintype "passive+no_connect"))
    )
    (net (code "181") (name "unconnected-(P3-Pad53)") (class "Default")
      (node (ref "P3") (pin "53") (pinfunction "53_53") (pintype "passive+no_connect"))
    )
    (net (code "182") (name "unconnected-(P3-Pad54)") (class "Default")
      (node (ref "P3") (pin "54") (pinfunction "54_54") (pintype "passive+no_connect"))
    )
    (net (code "183") (name "unconnected-(P3-Pad55)") (class "Default")
      (node (ref "P3") (pin "55") (pinfunction "55_55") (pintype "passive+no_connect"))
    )
    (net (code "184") (name "unconnected-(P3-Pad56)") (class "Default")
      (node (ref "P3") (pin "56") (pinfunction "56_56") (pintype "passive+no_connect"))
    )
    (net (code "185") (name "unconnected-(P3-Pad57)") (class "Default")
      (node (ref "P3") (pin "57") (pinfunction "57_57") (pintype "passive+no_connect"))
    )
    (net (code "186") (name "unconnected-(P3-Pad58)") (class "Default")
      (node (ref "P3") (pin "58") (pinfunction "58_58") (pintype "passive+no_connect"))
    )
    (net (code "187") (name "unconnected-(P4-Pad1)") (class "Default")
      (node (ref "P4") (pin "1") (pinfunction "1_1") (pintype "passive+no_connect"))
    )
    (net (code "188") (name "unconnected-(P4-Pad2)") (class "Default")
      (node (ref "P4") (pin "2") (pinfunction "2_2") (pintype "passive+no_connect"))
    )
    (net (code "189") (name "unconnected-(P4-Pad3)") (class "Default")
      (node (ref "P4") (pin "3") (pinfunction "3_3") (pintype "passive+no_connect"))
    )
    (net (code "190") (name "unconnected-(P4-Pad5)") (class "Default")
      (node (ref "P4") (pin "5") (pinfunction "5_5") (pintype "passive+no_connect"))
    )
    (net (code "191") (name "unconnected-(P4-Pad7)") (class "Default")
      (node (ref "P4") (pin "7") (pinfunction "7_7") (pintype "passive+no_connect"))
    )
    (net (code "192") (name "unconnected-(P4-Pad9)") (class "Default")
      (node (ref "P4") (pin "9") (pinfunction "9_9") (pintype "passive+no_connect"))
    )
    (net (code "193") (name "unconnected-(P4-Pad13)") (class "Default")
      (node (ref "P4") (pin "13") (pinfunction "13_13") (pintype "passive+no_connect"))
    )
    (net (code "194") (name "unconnected-(P4-Pad15)") (class "Default")
      (node (ref "P4") (pin "15") (pinfunction "15_15") (pintype "passive+no_connect"))
    )
    (net (code "195") (name "unconnected-(P4-Pad17)") (class "Default")
      (node (ref "P4") (pin "17") (pinfunction "17_17") (pintype "passive+no_connect"))
    )
    (net (code "196") (name "unconnected-(P4-Pad19)") (class "Default")
      (node (ref "P4") (pin "19") (pinfunction "19_19") (pintype "passive+no_connect"))
    )
    (net (code "197") (name "unconnected-(P4-Pad23)") (class "Default")
      (node (ref "P4") (pin "23") (pinfunction "23_23") (pintype "passive+no_connect"))
    )
    (net (code "198") (name "unconnected-(P4-Pad25)") (class "Default")
      (node (ref "P4") (pin "25") (pinfunction "25_25") (pintype "passive+no_connect"))
    )
    (net (code "199") (name "unconnected-(P4-Pad27)") (class "Default")
      (node (ref "P4") (pin "27") (pinfunction "27_27") (pintype "passive+no_connect"))
    )
    (net (code "200") (name "unconnected-(P4-Pad29)") (class "Default")
      (node (ref "P4") (pin "29") (pinfunction "29_29") (pintype "passive+no_connect"))
    )
    (net (code "201") (name "unconnected-(P4-Pad33)") (class "Default")
      (node (ref "P4") (pin "33") (pinfunction "33_33") (pintype "passive+no_connect"))
    )
    (net (code "202") (name "unconnected-(P4-Pad35)") (class "Default")
      (node (ref "P4") (pin "35") (pinfunction "35_35") (pintype "passive+no_connect"))
    )
    (net (code "203") (name "unconnected-(P4-Pad37)") (class "Default")
      (node (ref "P4") (pin "37") (pinfunction "37_37") (pintype "passive+no_connect"))
    )
    (net (code "204") (name "unconnected-(P4-Pad39)") (class "Default")
      (node (ref "P4") (pin "39") (pinfunction "39_39") (pintype "passive+no_connect"))
    )
    (net (code "205") (name "unconnected-(P4-Pad43)") (class "Default")
      (node (ref "P4") (pin "43") (pinfunction "43_43") (pintype "passive+no_connect"))
    )
    (net (code "206") (name "unconnected-(P4-Pad44)") (class "Default")
      (node (ref "P4") (pin "44") (pinfunction "44_44") (pintype "passive+no_connect"))
    )
    (net (code "207") (name "unconnected-(P4-Pad45)") (class "Default")
      (node (ref "P4") (pin "45") (pinfunction "45_45") (pintype "passive+no_connect"))
    )
    (net (code "208") (name "unconnected-(P4-Pad46)") (class "Default")
      (node (ref "P4") (pin "46") (pinfunction "46_46") (pintype "passive+no_connect"))
    )
    (net (code "209") (name "unconnected-(P4-Pad47)") (class "Default")
      (node (ref "P4") (pin "47") (pinfunction "47_47") (pintype "passive+no_connect"))
    )
    (net (code "210") (name "unconnected-(P4-Pad48)") (class "Default")
      (node (ref "P4") (pin "48") (pinfunction "48_48") (pintype "passive+no_connect"))
    )
    (net (code "211") (name "unconnected-(P4-Pad49)") (class "Default")
      (node (ref "P4") (pin "49") (pinfunction "49_49") (pintype "passive+no_connect"))
    )
    (net (code "212") (name "unconnected-(P4-Pad50)") (class "Default")
      (node (ref "P4") (pin "50") (pinfunction "50_50") (pintype "passive+no_connect"))
    )
    (net (code "213") (name "unconnected-(P4-Pad53)") (class "Default")
      (node (ref "P4") (pin "53") (pinfunction "53_53") (pintype "passive+no_connect"))
    )
    (net (code "214") (name "unconnected-(P4-Pad54)") (class "Default")
      (node (ref "P4") (pin "54") (pinfunction "54_54") (pintype "passive+no_connect"))
    )
    (net (code "215") (name "unconnected-(P4-Pad55)") (class "Default")
      (node (ref "P4") (pin "55") (pinfunction "55_55") (pintype "passive+no_connect"))
    )
    (net (code "216") (name "unconnected-(P4-Pad56)") (class "Default")
      (node (ref "P4") (pin "56") (pinfunction "56_56") (pintype "passive+no_connect"))
    )
    (net (code "217") (name "unconnected-(P4-Pad57)") (class "Default")
      (node (ref "P4") (pin "57") (pinfunction "57_57") (pintype "passive+no_connect"))
    )
    (net (code "218") (name "unconnected-(P4-Pad58)") (class "Default")
      (node (ref "P4") (pin "58") (pinfunction "58_58") (pintype "passive+no_connect"))
    )
    (net (code "219") (name "unconnected-(P4-Pad59)") (class "Default")
      (node (ref "P4") (pin "59") (pinfunction "59_59") (pintype "passive+no_connect"))
    )
    (net (code "220") (name "unconnected-(P4-Pad60)") (class "Default")
      (node (ref "P4") (pin "60") (pinfunction "60_60") (pintype "passive+no_connect"))
    )
    (net (code "221") (name "unconnected-(P5-Pad3)") (class "Default")
      (node (ref "P5") (pin "3") (pinfunction "3_3") (pintype "passive+no_connect"))
    )
    (net (code "222") (name "unconnected-(P5-Pad4)") (class "Default")
      (node (ref "P5") (pin "4") (pinfunction "4_4") (pintype "passive+no_connect"))
    )
    (net (code "223") (name "unconnected-(P5-Pad5)") (class "Default")
      (node (ref "P5") (pin "5") (pinfunction "5_5") (pintype "passive+no_connect"))
    )
    (net (code "224") (name "unconnected-(P5-Pad8)") (class "Default")
      (node (ref "P5") (pin "8") (pinfunction "8_8") (pintype "passive+no_connect"))
    )
    (net (code "225") (name "unconnected-(P5-Pad22)") (class "Default")
      (node (ref "P5") (pin "22") (pinfunction "22_22") (pintype "passive+no_connect"))
    )
    (net (code "226") (name "unconnected-(P5-Pad23)") (class "Default")
      (node (ref "P5") (pin "23") (pinfunction "23_23") (pintype "passive+no_connect"))
    )
    (net (code "227") (name "unconnected-(P6-Pad12)") (class "Default")
      (node (ref "P6") (pin "12") (pinfunction "12_12") (pintype "passive+no_connect"))
    )
    (net (code "228") (name "unconnected-(P6-Pad14)") (class "Default")
      (node (ref "P6") (pin "14") (pinfunction "14_14") (pintype "passive+no_connect"))
    )
  )
)
